# SCH-1-ESD_Power_Rails.net
KiCad netlist of a schematic drawn in Altium Designer
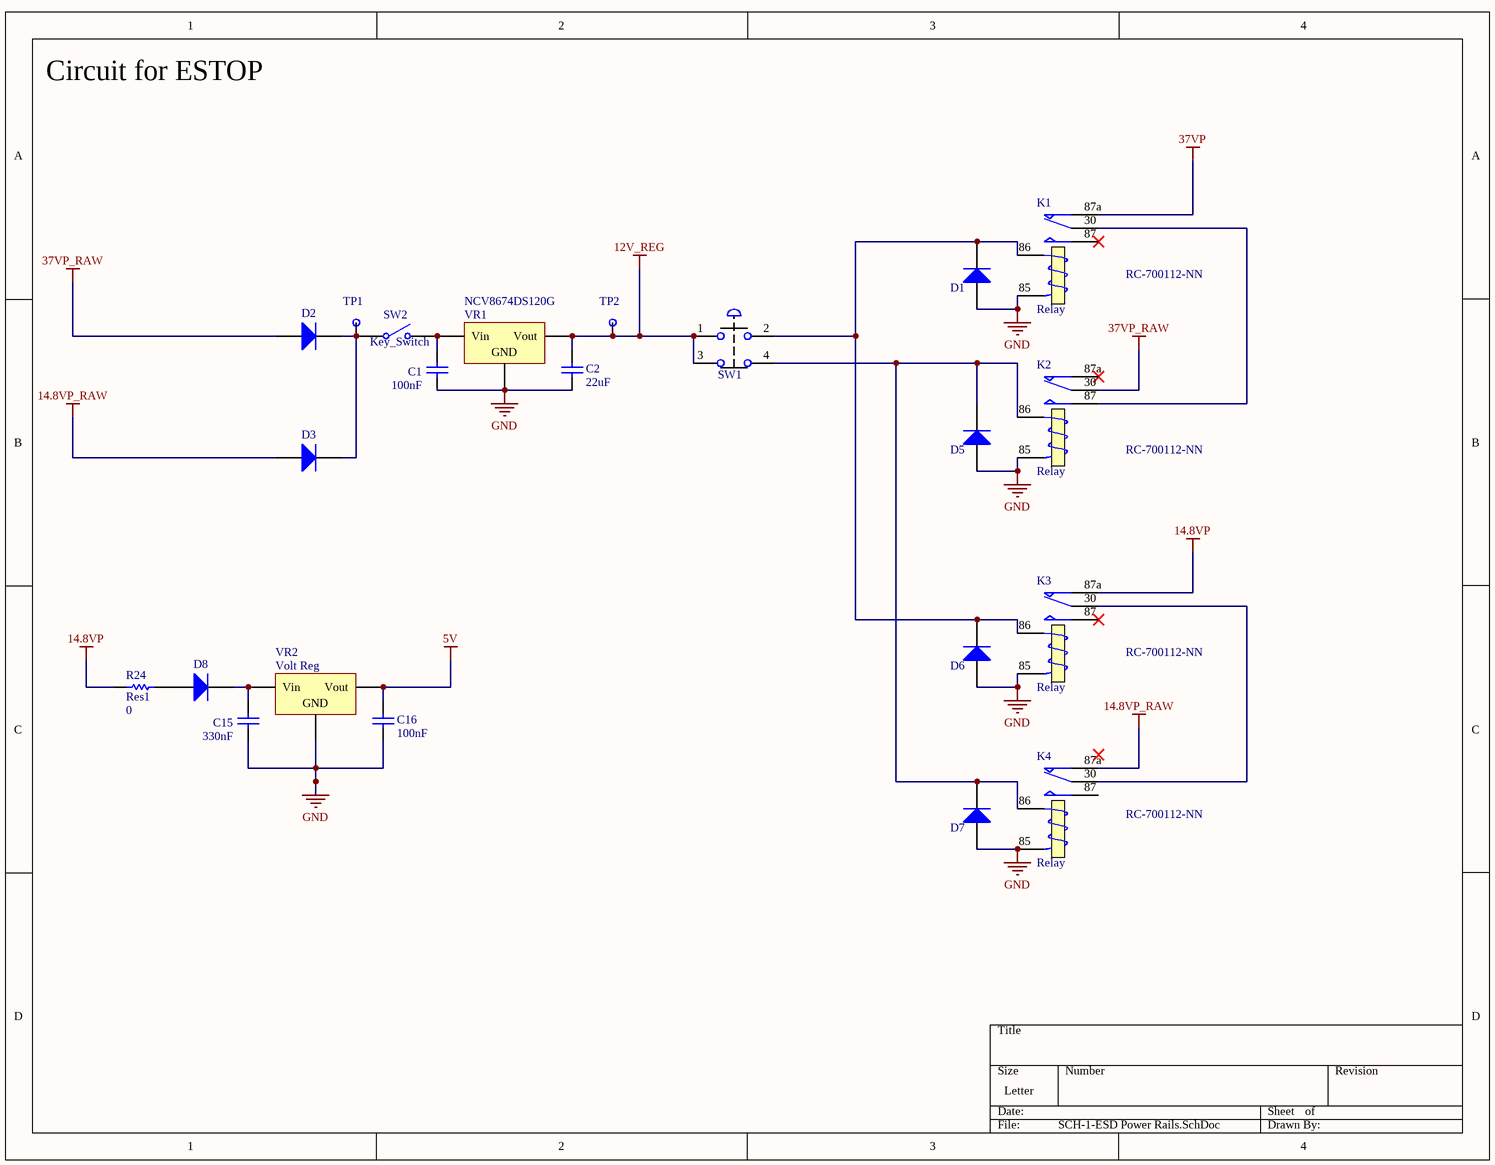
[diagram p0: SCH-1-ESD Power Rails.SchDoc]

(export (version "E")
  (design (tool "Eeschema 10.0.6"))
  (components
    (comp (ref "C1")
      (value "100nF")
      (footprint "1608[0603]")
      (description "Capacitor")
      (fields (field (name "Comment") "Cap") (field (name "PUBLISHER") "Altium Limited"))
      (libsource (lib "Miscellaneous Devices") (part "Cap"))
    )
    (comp (ref "C2")
      (value "22uF")
      (footprint "1608[0603]")
      (description "Capacitor")
      (fields (field (name "Comment") "Cap") (field (name "PUBLISHER") "Altium Limited"))
      (libsource (lib "Miscellaneous Devices") (part "Cap"))
    )
    (comp (ref "C15")
      (value "330nF")
      (footprint "1608[0603]")
      (description "Capacitor")
      (fields (field (name "Comment") "Cap") (field (name "PUBLISHER") "Altium Limited"))
      (libsource (lib "Miscellaneous Devices") (part "Cap"))
    )
    (comp (ref "C16")
      (value "100nF")
      (footprint "1608[0603]")
      (description "Capacitor")
      (fields (field (name "Comment") "Cap") (field (name "PUBLISHER") "Altium Limited"))
      (libsource (lib "Miscellaneous Devices") (part "Cap"))
    )
    (comp (ref "D1")
      (value "Diode 1N4001")
      (footprint "DO-41")
      (description "1 Amp General Purpose Rectifier")
      (fields (field (name "PUBLISHER") "Altium Limited"))
      (libsource (lib "Miscellaneous Devices") (part "Diode 1N4001"))
    )
    (comp (ref "D2")
      (value "Diode 1N4001")
      (footprint "DO-41")
      (description "1 Amp General Purpose Rectifier")
      (fields (field (name "PUBLISHER") "Altium Limited"))
      (libsource (lib "Miscellaneous Devices") (part "Diode 1N4001"))
    )
    (comp (ref "D3")
      (value "Diode 1N4001")
      (footprint "DO-41")
      (description "1 Amp General Purpose Rectifier")
      (fields (field (name "PUBLISHER") "Altium Limited"))
      (libsource (lib "Miscellaneous Devices") (part "Diode 1N4001"))
    )
    (comp (ref "D5")
      (value "Diode 1N4001")
      (footprint "DO-41")
      (description "1 Amp General Purpose Rectifier")
      (fields (field (name "PUBLISHER") "Altium Limited"))
      (libsource (lib "Miscellaneous Devices") (part "Diode 1N4001"))
    )
    (comp (ref "D6")
      (value "Diode 1N4001")
      (footprint "DO-41")
      (description "1 Amp General Purpose Rectifier")
      (fields (field (name "PUBLISHER") "Altium Limited"))
      (libsource (lib "Miscellaneous Devices") (part "Diode 1N4001"))
    )
    (comp (ref "D7")
      (value "Diode 1N4001")
      (footprint "DO-41")
      (description "1 Amp General Purpose Rectifier")
      (fields (field (name "PUBLISHER") "Altium Limited"))
      (libsource (lib "Miscellaneous Devices") (part "Diode 1N4001"))
    )
    (comp (ref "D8")
      (value "Diode 1N4001")
      (footprint "DO-41")
      (description "1 Amp General Purpose Rectifier")
      (fields (field (name "PUBLISHER") "Altium Limited"))
      (libsource (lib "Miscellaneous Devices") (part "Diode 1N4001"))
    )
    (comp (ref "K1")
      (value "Relay")
      (footprint "Relay RC-700112-NN")
      (description "SPDT Relay")
      (fields (field (name "PUBLISHER") "Altium Limited"))
      (libsource (lib "RSX_Relays") (part "Relay"))
    )
    (comp (ref "K2")
      (value "Relay")
      (footprint "Relay RC-700112-NN")
      (description "SPDT Relay")
      (fields (field (name "PUBLISHER") "Altium Limited"))
      (libsource (lib "RSX_Relays") (part "Relay"))
    )
    (comp (ref "K3")
      (value "Relay")
      (footprint "Relay RC-700112-NN")
      (description "SPDT Relay")
      (fields (field (name "PUBLISHER") "Altium Limited"))
      (libsource (lib "RSX_Relays") (part "Relay"))
    )
    (comp (ref "K4")
      (value "Relay")
      (footprint "Relay RC-700112-NN")
      (description "SPDT Relay")
      (fields (field (name "PUBLISHER") "Altium Limited"))
      (libsource (lib "RSX_Relays") (part "Relay"))
    )
    (comp (ref "R24")
      (value "Res1")
      (footprint "AXIAL-0.3")
      (description "Resistor")
      (fields (field (name "ALTIUM_VALUE") "0") (field (name "PUBLISHER") "Altium Limited"))
      (libsource (lib "Miscellaneous Devices") (part "Res1"))
    )
    (comp (ref "SW1")
      (value "NO-NC ESD with light")
      (footprint "MOLEX 0039281043")
      (libsource (lib "RSX_Miscellaneous") (part "DPST ESTOP"))
    )
    (comp (ref "SW2")
      (value "Key_Switch")
      (footprint "MOLEX_0039293026")
      (fields (field (name "PUBLISHER") "Altium Limited"))
      (libsource (lib "RSX_Miscellaneous") (part "Key_Switch"))
    )
    (comp (ref "TP1")
      (value "TestPt")
      (footprint "50_MIL_PAD")
      (libsource (lib "RSX_Test_Points") (part "TestPt"))
    )
    (comp (ref "TP2")
      (value "TestPt")
      (footprint "50_MIL_PAD")
      (libsource (lib "RSX_Test_Points") (part "TestPt"))
    )
    (comp (ref "VR1")
      (value "Volt Reg")
      (footprint "DPAK254P1420X457-3N")
      (description "Voltage Regulator")
      (fields (field (name "PUBLISHER") "Altium Limited"))
      (libsource (lib "RSX_ICs") (part "Volt Reg"))
    )
    (comp (ref "VR2")
      (value "Volt Reg")
      (footprint "D2PAK_N")
      (description "Voltage Regulator")
      (fields (field (name "PUBLISHER") "Altium Limited"))
      (libsource (lib "Miscellaneous Devices") (part "Volt Reg"))
    )
  )
  (nets
    (net (code "1") (name "5V") (class "Default")
      (node (ref "C16") (pin "1") (pinfunction "1_1") (pintype "passive"))
      (node (ref "VR2") (pin "3") (pinfunction "Vout_3") (pintype "passive"))
    )
    (net (code "2") (name "12V_REG") (class "Default")
      (node (ref "C2") (pin "1") (pinfunction "1_1") (pintype "passive"))
      (node (ref "SW1") (pin "1") (pintype "passive"))
      (node (ref "SW1") (pin "3") (pintype "passive"))
      (node (ref "TP2") (pin "1") (pinfunction "1_1") (pintype "passive"))
      (node (ref "VR1") (pin "3") (pinfunction "Vout_3") (pintype "passive"))
    )
    (net (code "3") (name "14.8VP") (class "Default")
      (node (ref "K3") (pin "87a") (pinfunction "NC_87a") (pintype "passive"))
      (node (ref "R24") (pin "1") (pinfunction "1_1") (pintype "passive"))
    )
    (net (code "4") (name "14.8VP_RAW") (class "Default")
      (node (ref "D3") (pin "1") (pinfunction "A_1") (pintype "passive"))
      (node (ref "K4") (pin "87a") (pinfunction "NC_87a") (pintype "passive"))
    )
    (net (code "5") (name "37VP") (class "Default")
      (node (ref "K1") (pin "87a") (pinfunction "NC_87a") (pintype "passive"))
    )
    (net (code "6") (name "37VP_RAW") (class "Default")
      (node (ref "D2") (pin "1") (pinfunction "A_1") (pintype "passive"))
      (node (ref "K2") (pin "30") (pinfunction "COM_30") (pintype "passive"))
    )
    (net (code "7") (name "GND") (class "Default")
      (node (ref "C1") (pin "2") (pinfunction "2_2") (pintype "passive"))
      (node (ref "C15") (pin "2") (pinfunction "2_2") (pintype "passive"))
      (node (ref "C16") (pin "2") (pinfunction "2_2") (pintype "passive"))
      (node (ref "C2") (pin "2") (pinfunction "2_2") (pintype "passive"))
      (node (ref "D1") (pin "1") (pinfunction "A_1") (pintype "passive"))
      (node (ref "D5") (pin "1") (pinfunction "A_1") (pintype "passive"))
      (node (ref "D6") (pin "1") (pinfunction "A_1") (pintype "passive"))
      (node (ref "D7") (pin "1") (pinfunction "A_1") (pintype "passive"))
      (node (ref "K1") (pin "85") (pinfunction "T2_85") (pintype "passive"))
      (node (ref "K2") (pin "85") (pinfunction "T2_85") (pintype "passive"))
      (node (ref "K3") (pin "85") (pinfunction "T2_85") (pintype "passive"))
      (node (ref "K4") (pin "85") (pinfunction "T2_85") (pintype "passive"))
      (node (ref "VR1") (pin "2") (pinfunction "GND_2") (pintype "passive"))
      (node (ref "VR2") (pin "2") (pinfunction "GND_2") (pintype "passive"))
    )
    (net (code "8") (name "Net-(D1-K)") (class "Default")
      (node (ref "D1") (pin "2") (pinfunction "K_2") (pintype "passive"))
      (node (ref "D6") (pin "2") (pinfunction "K_2") (pintype "passive"))
      (node (ref "K1") (pin "86") (pinfunction "T1_86") (pintype "passive"))
      (node (ref "K3") (pin "86") (pinfunction "T1_86") (pintype "passive"))
      (node (ref "SW1") (pin "2") (pintype "passive"))
    )
    (net (code "9") (name "Net-(D2-K)") (class "Default")
      (node (ref "D2") (pin "2") (pinfunction "K_2") (pintype "passive"))
      (node (ref "D3") (pin "2") (pinfunction "K_2") (pintype "passive"))
      (node (ref "SW2") (pin "1") (pinfunction "COMMON_1") (pintype "passive"))
      (node (ref "TP1") (pin "1") (pinfunction "1_1") (pintype "passive"))
    )
    (net (code "10") (name "Net-(D5-K)") (class "Default")
      (node (ref "D5") (pin "2") (pinfunction "K_2") (pintype "passive"))
      (node (ref "D7") (pin "2") (pinfunction "K_2") (pintype "passive"))
      (node (ref "K2") (pin "86") (pinfunction "T1_86") (pintype "passive"))
      (node (ref "K4") (pin "86") (pinfunction "T1_86") (pintype "passive"))
      (node (ref "SW1") (pin "4") (pintype "passive"))
    )
    (net (code "11") (name "Net-(D8-A)") (class "Default")
      (node (ref "D8") (pin "1") (pinfunction "A_1") (pintype "passive"))
      (node (ref "R24") (pin "2") (pinfunction "2_2") (pintype "passive"))
    )
    (net (code "12") (name "Net-(D8-K)") (class "Default")
      (node (ref "C15") (pin "1") (pinfunction "1_1") (pintype "passive"))
      (node (ref "D8") (pin "2") (pinfunction "K_2") (pintype "passive"))
      (node (ref "VR2") (pin "1") (pinfunction "Vin_1") (pintype "passive"))
    )
    (net (code "13") (name "Net-(K1-COM)") (class "Default")
      (node (ref "K1") (pin "30") (pinfunction "COM_30") (pintype "passive"))
      (node (ref "K2") (pin "87") (pinfunction "NO_87") (pintype "passive"))
    )
    (net (code "14") (name "Net-(K3-COM)") (class "Default")
      (node (ref "K3") (pin "30") (pinfunction "COM_30") (pintype "passive"))
      (node (ref "K4") (pin "30") (pinfunction "COM_30") (pintype "passive"))
    )
    (net (code "15") (name "Net-(SW2-NO)") (class "Default")
      (node (ref "C1") (pin "1") (pinfunction "1_1") (pintype "passive"))
      (node (ref "SW2") (pin "2") (pinfunction "NO_2") (pintype "passive"))
      (node (ref "VR1") (pin "1") (pinfunction "Vin_1") (pintype "passive"))
    )
    (net (code "16") (name "unconnected-(K1-NO-Pad87)") (class "Default")
      (node (ref "K1") (pin "87") (pinfunction "NO_87") (pintype "passive+no_connect"))
    )
    (net (code "17") (name "unconnected-(K2-NC-Pad87a)") (class "Default")
      (node (ref "K2") (pin "87a") (pinfunction "NC_87a") (pintype "passive+no_connect"))
    )
    (net (code "18") (name "unconnected-(K3-NO-Pad87)") (class "Default")
      (node (ref "K3") (pin "87") (pinfunction "NO_87") (pintype "passive+no_connect"))
    )
    (net (code "19") (name "unconnected-(K4-NO-Pad87)") (class "Default")
      (node (ref "K4") (pin "87") (pinfunction "NO_87") (pintype "passive"))
    )
  )
)
